# Power-SMPS.net
KiCad netlist of a schematic drawn in Altium Designer
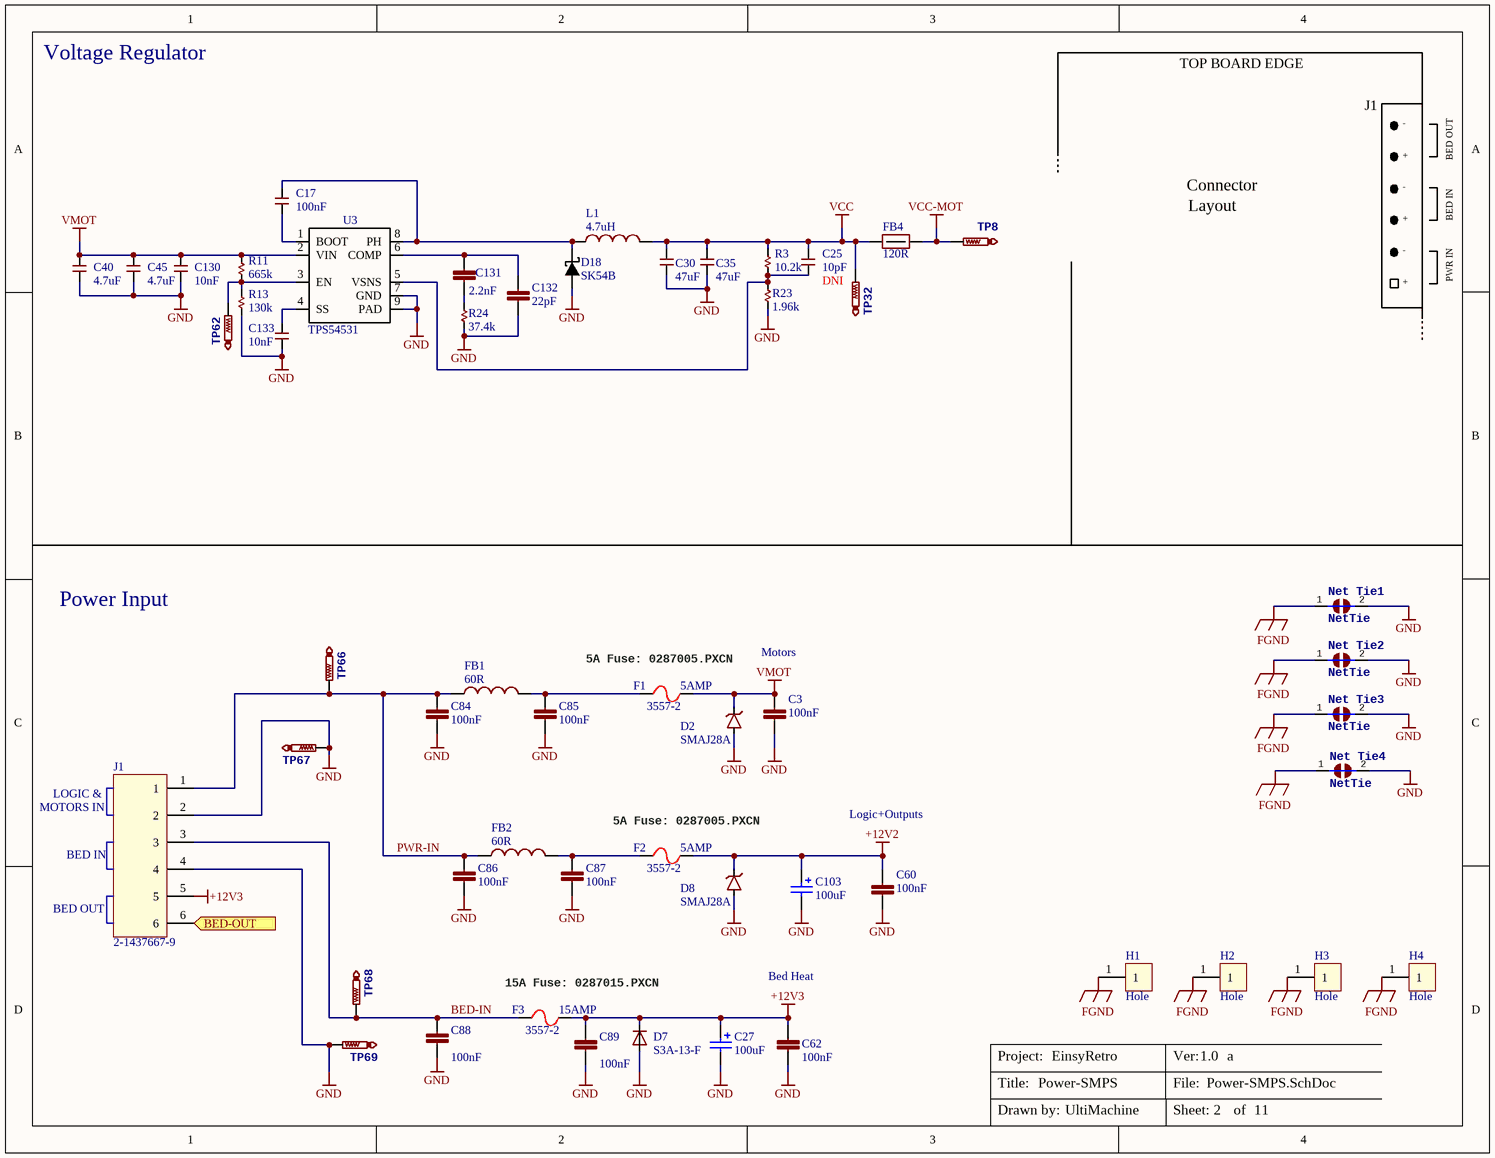
[diagram p0: Power-SMPS.SchDoc]

(export (version "E")
  (design (tool "Eeschema 10.0.6"))
  (components
    (comp (ref "C3")
      (value "100nF")
      (footprint "C0603")
      (description "CAP CER 0603 100nF 50V 10% X7R")
      (fields (field (name "MANUFACTURER") "Kemet") (field (name "TOLERANCE") "+/- 10%"))
      (libsource (lib "3Delight") (part "C0603C104K5RACTU"))
    )
    (comp (ref "C17")
      (value "100nF")
      (footprint "C0603")
      (description "CAP CER 0603 100nF 50V 10% X7R")
      (fields (field (name "MANUFACTURER") "Kemet") (field (name "TOLERANCE") "+/- 10%"))
      (libsource (lib "Capacitors") (part "100nF 0603 50V X7R"))
    )
    (comp (ref "C25")
      (value "10pF")
      (footprint "C0402")
      (description "CAP CER 10PF 50V 5% NP0 0402")
      (fields
        (field (name "TOLERANCE") "5%")
        (field (name "MANUFACTURER") "Samsung")
        (field (name "DNI") "DNI")
      )
      (libsource (lib "Capacitors") (part "10pF 0402 50V NP0"))
    )
    (comp (ref "C27")
      (value "100uF")
      (footprint "CAP-ELEC-063063077")
      (description "CAP ALUM 100UF 35V 20% SMD")
      (fields (field (name "MANUFACTURER") "Nichicon") (field (name "TOLERANCE") "+/- 20%"))
      (libsource (lib "3Delight") (part "UWT1V101MCL1GS"))
    )
    (comp (ref "C30")
      (value "47uF")
      (footprint "C1210")
      (description "CAP CER 47UF 10V X5R 1210")
      (fields (field (name "MANUFACTURER") "Murata") (field (name "TOLERANCE") "10%"))
      (libsource (lib "Capacitors") (part "47uF 1210 10V X5R"))
    )
    (comp (ref "C35")
      (value "47uF")
      (footprint "C1210")
      (description "CAP CER 47UF 10V X5R 1210")
      (fields (field (name "MANUFACTURER") "Murata") (field (name "TOLERANCE") "10%"))
      (libsource (lib "Capacitors") (part "47uF 1210 10V X5R"))
    )
    (comp (ref "C40")
      (value "4.7uF")
      (footprint "C1210")
      (description "CAP CER 4.7UF 50V X7R 1210")
      (fields (field (name "MANUFACTURER") "Murata") (field (name "PART") "4.7uF 1210 50V X7R"))
      (libsource (lib "Capacitors") (part "4.7uF 1210 50V X7R"))
    )
    (comp (ref "C45")
      (value "4.7uF")
      (footprint "C1210")
      (description "CAP CER 4.7UF 50V X7R 1210")
      (fields (field (name "MANUFACTURER") "Murata") (field (name "PART") "4.7uF 1210 50V X7R"))
      (libsource (lib "Capacitors") (part "4.7uF 1210 50V X7R"))
    )
    (comp (ref "C60")
      (value "100nF")
      (footprint "C0603")
      (description "CAP CER 0603 100nF 50V 10% X7R")
      (fields (field (name "MANUFACTURER") "Kemet") (field (name "TOLERANCE") "+/- 10%"))
      (libsource (lib "3Delight") (part "C0603C104K5RACTU"))
    )
    (comp (ref "C62")
      (value "100nF")
      (footprint "C0603")
      (description "CAP CER 0603 100nF 50V 10% X7R")
      (fields (field (name "MANUFACTURER") "Kemet") (field (name "TOLERANCE") "+/- 10%"))
      (libsource (lib "3Delight") (part "C0603C104K5RACTU"))
    )
    (comp (ref "C84")
      (value "100nF")
      (footprint "C0603")
      (description "CAP CER 0603 100nF 50V 10% X7R")
      (fields (field (name "MANUFACTURER") "Kemet") (field (name "TOLERANCE") "+/- 10%"))
      (libsource (lib "3Delight") (part "C0603C104K5RACTU"))
    )
    (comp (ref "C85")
      (value "100nF")
      (footprint "C0603")
      (description "CAP CER 0603 100nF 50V 10% X7R")
      (fields (field (name "MANUFACTURER") "Kemet") (field (name "TOLERANCE") "+/- 10%"))
      (libsource (lib "3Delight") (part "C0603C104K5RACTU"))
    )
    (comp (ref "C86")
      (value "100nF")
      (footprint "C0603")
      (description "CAP CER 0603 100nF 50V 10% X7R")
      (fields (field (name "MANUFACTURER") "Kemet") (field (name "TOLERANCE") "+/- 10%"))
      (libsource (lib "3Delight") (part "C0603C104K5RACTU"))
    )
    (comp (ref "C87")
      (value "100nF")
      (footprint "C0603")
      (description "CAP CER 0603 100nF 50V 10% X7R")
      (fields (field (name "MANUFACTURER") "Kemet") (field (name "TOLERANCE") "+/- 10%"))
      (libsource (lib "3Delight") (part "C0603C104K5RACTU"))
    )
    (comp (ref "C88")
      (value "100nF")
      (footprint "C0603")
      (description "CAP CER 0603 100nF 50V 10% X7R")
      (fields (field (name "MANUFACTURER") "Kemet") (field (name "TOLERANCE") "+/- 10%"))
      (libsource (lib "3Delight") (part "C0603C104K5RACTU"))
    )
    (comp (ref "C89")
      (value "100nF")
      (footprint "C0603")
      (description "CAP CER 0603 100nF 50V 10% X7R")
      (fields (field (name "MANUFACTURER") "Kemet") (field (name "TOLERANCE") "+/- 10%"))
      (libsource (lib "3Delight") (part "C0603C104K5RACTU"))
    )
    (comp (ref "C103")
      (value "100uF")
      (footprint "CAP-ELEC-063063077")
      (description "CAP ALUM 100UF 35V 20% SMD")
      (fields (field (name "MANUFACTURER") "Nichicon") (field (name "TOLERANCE") "+/- 20%"))
      (libsource (lib "3Delight") (part "UWT1V101MCL1GS"))
    )
    (comp (ref "C130")
      (value "10nF")
      (footprint "C0402")
      (description "CAP CER 10nF 50V X7R 0402")
      (fields (field (name "TOLERANCE") "5%") (field (name "MANUFACTURER") "Murata"))
      (libsource (lib "Capacitors") (part "10nF 0402 50V X7R"))
    )
    (comp (ref "C131")
      (value "2.2nF")
      (footprint "C0402")
      (description "CAP CER 0402 2.2nF 25V C0G")
      (fields (field (name "MANUFACTURER") "Kemet") (field (name "PART") "2.2nF 25V C0G 0402"))
      (libsource (lib "Capacitors") (part "2.2nF 25V C0G 0402"))
    )
    (comp (ref "C132")
      (value "22pF")
      (footprint "C0402")
      (description "CAP CER 0402 22pF 50V 5% C0G")
      (fields (field (name "MANUFACTURER") "AVX") (field (name "PART") "22pF 50V"))
      (libsource (lib "Capacitors") (part "22pF 0402 50V C0G"))
    )
    (comp (ref "C133")
      (value "10nF")
      (footprint "C0402")
      (description "CAP CER 10nF 50V X7R 0402")
      (fields (field (name "TOLERANCE") "5%") (field (name "MANUFACTURER") "Murata"))
      (libsource (lib "Capacitors") (part "10nF 0402 50V X7R"))
    )
    (comp (ref "D2")
      (value "SMAJ28A")
      (footprint "SMA-SM")
      (description "TVS DIODE 28VWM 45.4VC SMA")
      (fields (field (name "MANUFACTURER") "Diodes Inc") (field (name "TOLERANCE") "NA"))
      (libsource (lib "Diodes") (part "SMAJ28A"))
    )
    (comp (ref "D7")
      (value "S3A-13-F")
      (footprint "DO-214AB")
      (description "DIODE DO-214AB")
      (fields (field (name "MANUFACTURER") "Diodes Incorporated") (field (name "TOLERANCE") "NA"))
      (libsource (lib "3Delight") (part "S3A-13-F"))
    )
    (comp (ref "D8")
      (value "SMAJ28A")
      (footprint "SMA-SM")
      (description "TVS DIODE 28VWM 45.4VC SMA")
      (fields (field (name "MANUFACTURER") "Diodes Inc") (field (name "TOLERANCE") "NA"))
      (libsource (lib "Diodes") (part "SMAJ28A"))
    )
    (comp (ref "D18")
      (value "SK54B")
      (footprint "SMB_DO-214AA_LRG")
      (description "DIODE SCHOTTKY 40V 5A SMB_DO214AA")
      (fields (field (name "MANUFACTURER") "MCC") (field (name "VOLTAGE") "40Vrb"))
      (libsource (lib "Diodes") (part "SK54B"))
    )
    (comp (ref "F1")
      (value "3557-2")
      (footprint "3557")
      (description "FUSE PTH ATO")
      (fields (field (name "MANUFACTURER") "Keystone") (field (name "PART") "Fuse"))
      (libsource (lib "3Delight") (part "3557-2"))
    )
    (comp (ref "F2")
      (value "3557-2")
      (footprint "3557")
      (description "FUSE PTH ATO")
      (fields (field (name "MANUFACTURER") "Keystone") (field (name "PART") "Fuse"))
      (libsource (lib "3Delight") (part "3557-2"))
    )
    (comp (ref "F3")
      (value "3557-2")
      (footprint "3557")
      (description "FUSE PTH ATO")
      (fields (field (name "MANUFACTURER") "Keystone") (field (name "PART") "Fuse"))
      (libsource (lib "3Delight") (part "3557-2"))
    )
    (comp (ref "FB1")
      (value "60R")
      (footprint "3Delight:L1806")
      (description "FERRITE BEAD 1806 60ohm")
      (fields (field (name "MANUFACTURER") "Murata") (field (name "PART") "60Rf"))
      (libsource (lib "3Delight") (part "BLM41PG600SN1L"))
    )
    (comp (ref "FB2")
      (value "60R")
      (footprint "3Delight:L1806")
      (description "FERRITE BEAD 1806 60ohm")
      (fields (field (name "MANUFACTURER") "Murata") (field (name "PART") "60Rf"))
      (libsource (lib "3Delight") (part "BLM41PG600SN1L"))
    )
    (comp (ref "FB4")
      (value "120R")
      (footprint "FB0603")
      (description "FERRITE BEAD 120 OHM 0603 1LN")
      (fields (field (name "MANUFACTURER") "Samsung") (field (name "PART") "FERRITE 120R 3A 0603"))
      (libsource (lib "3Delight") (part "FERRITE 220R 2.5A 0603"))
    )
    (comp (ref "H1")
      (value "Hole")
      (footprint "Wave_hole_3x7-singleSided")
      (libsource (lib "3Delight") (part "Hole"))
    )
    (comp (ref "H2")
      (value "Hole")
      (footprint "Wave_hole_3x7-singleSided")
      (libsource (lib "3Delight") (part "Hole"))
    )
    (comp (ref "H3")
      (value "Hole")
      (footprint "Wave_hole_3x7-singleSided")
      (libsource (lib "3Delight") (part "Hole"))
    )
    (comp (ref "H4")
      (value "Hole")
      (footprint "Wave_hole_3x7-singleSided")
      (libsource (lib "3Delight") (part "Hole"))
    )
    (comp (ref "J1")
      (value "2-1437667-9")
      (footprint "CON-Barrier-6-8.26mm")
      (description "CONN BARRIER STRIP 6CIRC 0.325\"")
      (fields (field (name "MANUFACTURER") "TE") (field (name "PART") "6POS"))
      (libsource (lib "3Delight") (part "2-1437667-9"))
    )
    (comp (ref "L1")
      (value "4.7uH")
      (footprint "IND_10X10")
      (description "FIXED IND 4.7UH 10A 15.5 MOHM")
      (fields (field (name "MANUFACTURER") "Bourns") (field (name "PART") "4.7uH 10A"))
      (libsource (lib "Inductors") (part "4.7uH 10A"))
    )
    (comp (ref "Net Tie1")
      (value "NetTie")
      (footprint "Net Tie")
      (description "Net Tie")
      (fields (field (name "PUBLISHER") "UltiMachine"))
      (libsource (lib "3Delight") (part "NetTie"))
    )
    (comp (ref "Net Tie2")
      (value "NetTie")
      (footprint "Net Tie")
      (description "Net Tie")
      (fields (field (name "PUBLISHER") "UltiMachine"))
      (libsource (lib "3Delight") (part "NetTie"))
    )
    (comp (ref "Net Tie3")
      (value "NetTie")
      (footprint "Net Tie")
      (description "Net Tie")
      (fields (field (name "PUBLISHER") "UltiMachine"))
      (libsource (lib "3Delight") (part "NetTie"))
    )
    (comp (ref "Net Tie4")
      (value "NetTie")
      (footprint "Net Tie")
      (description "Net Tie")
      (fields (field (name "PUBLISHER") "UltiMachine"))
      (libsource (lib "3Delight") (part "NetTie"))
    )
    (comp (ref "R3")
      (value "10.2k")
      (footprint "R0402")
      (description "RES SMD 10.2K OHM 1% 1/16W 0402")
      (fields (field (name "MANUFACTURER") "Yageo") (field (name "PART") "10.2k 1% 0402"))
      (libsource (lib "Resistors") (part "10.2k 1% 0402"))
    )
    (comp (ref "R11")
      (value "665k")
      (footprint "R0402")
      (description "RES SMD 665K OHM 1% 1/16W 0402")
      (fields (field (name "MANUFACTURER") "Yageo") (field (name "PART") "665k 1% 0402"))
      (libsource (lib "Resistors") (part "665k 1% 0402"))
    )
    (comp (ref "R13")
      (value "130k")
      (footprint "Passives:R0402")
      (description "RES SMD 130K OHM 5% 1/16W 0402")
      (fields (field (name "MANUFACTURER") "Yageo") (field (name "PART") "130k 1% 0402"))
      (libsource (lib "Resistors") (part "130k 1% 0402"))
    )
    (comp (ref "R23")
      (value "1.96k")
      (footprint "R0402")
      (description "RES SMD 1.96K OHM 1% 1/16W 0402")
      (fields (field (name "MANUFACTURER") "Yageo") (field (name "PART") "1.96k 1% 0402"))
      (libsource (lib "Resistors") (part "1.96k 1% 0402"))
    )
    (comp (ref "R24")
      (value "37.4k")
      (footprint "R0402")
      (description "RES SMD 37.4K OHM 1% 1/16W 0402")
      (fields (field (name "MANUFACTURER") "Yageo") (field (name "TOLERANCE") "1%"))
      (libsource (lib "Resistors") (part "37.4K 1% 0402"))
    )
    (comp (ref "TP8")
      (value "TestPoint")
      (footprint "TP1-27")
      (description "Test Point")
      (libsource (lib "3Delight") (part "TestPoint"))
    )
    (comp (ref "TP32")
      (value "TestPoint")
      (footprint "TP1-27")
      (description "Test Point")
      (libsource (lib "") (part "TestPoint_2"))
    )
    (comp (ref "TP62")
      (value "TestPoint")
      (footprint "TP1-27")
      (description "Test Point")
      (libsource (lib "") (part "TestPoint_2"))
    )
    (comp (ref "TP66")
      (value "TestPoint")
      (footprint "TP1-27")
      (description "Test Point")
      (libsource (lib "") (part "TestPoint_1"))
    )
    (comp (ref "TP67")
      (value "TestPoint")
      (footprint "TP1-27")
      (description "Test Point")
      (libsource (lib "") (part "TestPoint_3"))
    )
    (comp (ref "TP68")
      (value "TestPoint")
      (footprint "TP1-27")
      (description "Test Point")
      (libsource (lib "") (part "TestPoint_1"))
    )
    (comp (ref "TP69")
      (value "TestPoint")
      (footprint "TP1-27")
      (description "Test Point")
      (libsource (lib "3Delight") (part "TestPoint"))
    )
    (comp (ref "U3")
      (value "TPS54531")
      (footprint "SOIC127P600X170_HS-9L")
      (description "IC REG BUCK ADJ 5A 8SOPWRPAD")
      (fields (field (name "MANUFACTURER") "TI"))
      (libsource (lib "ICs-Power") (part "TPS54531"))
    )
  )
  (nets
    (net (code "1") (name "+12V2") (class "Default")
      (node (ref "C103") (pin "1") (pinfunction "1_1") (pintype "passive"))
      (node (ref "C60") (pin "1") (pinfunction "1_1") (pintype "passive"))
      (node (ref "D8") (pin "K") (pinfunction "K_K") (pintype "passive"))
      (node (ref "F2") (pin "2") (pinfunction "2_2") (pintype "passive"))
    )
    (net (code "2") (name "+12V3") (class "Default")
      (node (ref "C27") (pin "1") (pinfunction "1_1") (pintype "passive"))
      (node (ref "C62") (pin "1") (pinfunction "1_1") (pintype "passive"))
      (node (ref "C89") (pin "1") (pinfunction "1_1") (pintype "passive"))
      (node (ref "D7") (pin "C") (pinfunction "C_C") (pintype "passive"))
      (node (ref "F3") (pin "2") (pinfunction "2_2") (pintype "passive"))
      (node (ref "J1") (pin "5") (pinfunction "5_5") (pintype "passive"))
    )
    (net (code "3") (name "/BED-IN") (class "Default")
      (node (ref "C88") (pin "1") (pinfunction "1_1") (pintype "passive"))
      (node (ref "F3") (pin "1") (pinfunction "1_1") (pintype "passive"))
      (node (ref "J1") (pin "3") (pinfunction "3_3") (pintype "passive"))
      (node (ref "TP68") (pin "TP") (pinfunction "TP_TP") (pintype "passive"))
    )
    (net (code "4") (name "/BED-OUT") (class "Default")
      (node (ref "J1") (pin "6") (pinfunction "6_6") (pintype "passive"))
    )
    (net (code "5") (name "/PWR-IN") (class "Default")
      (node (ref "C84") (pin "1") (pinfunction "1_1") (pintype "passive"))
      (node (ref "C86") (pin "1") (pinfunction "1_1") (pintype "passive"))
      (node (ref "FB1") (pin "1") (pinfunction "1_1") (pintype "passive"))
      (node (ref "FB2") (pin "1") (pinfunction "1_1") (pintype "passive"))
      (node (ref "J1") (pin "1") (pinfunction "1_1") (pintype "passive"))
      (node (ref "TP66") (pin "TP") (pinfunction "TP_TP") (pintype "passive"))
    )
    (net (code "6") (name "FGND") (class "Default")
      (node (ref "H1") (pin "1") (pinfunction "1_1") (pintype "power_in"))
      (node (ref "H2") (pin "1") (pinfunction "1_1") (pintype "power_in"))
      (node (ref "H3") (pin "1") (pinfunction "1_1") (pintype "power_in"))
      (node (ref "H4") (pin "1") (pinfunction "1_1") (pintype "power_in"))
      (node (ref "Net Tie1") (pin "1") (pinfunction "1_1") (pintype "passive"))
      (node (ref "Net Tie2") (pin "1") (pinfunction "1_1") (pintype "passive"))
      (node (ref "Net Tie3") (pin "1") (pinfunction "1_1") (pintype "passive"))
      (node (ref "Net Tie4") (pin "1") (pinfunction "1_1") (pintype "passive"))
    )
    (net (code "7") (name "GND") (class "Default")
      (node (ref "C103") (pin "2") (pinfunction "2_2") (pintype "passive"))
      (node (ref "C130") (pin "1") (pinfunction "1_1") (pintype "passive"))
      (node (ref "C132") (pin "1") (pinfunction "1_1") (pintype "passive"))
      (node (ref "C133") (pin "1") (pinfunction "1_1") (pintype "passive"))
      (node (ref "C27") (pin "2") (pinfunction "2_2") (pintype "passive"))
      (node (ref "C3") (pin "2") (pinfunction "2_2") (pintype "passive"))
      (node (ref "C30") (pin "1") (pinfunction "1_1") (pintype "passive"))
      (node (ref "C35") (pin "1") (pinfunction "1_1") (pintype "passive"))
      (node (ref "C40") (pin "1") (pinfunction "1_1") (pintype "passive"))
      (node (ref "C45") (pin "1") (pinfunction "1_1") (pintype "passive"))
      (node (ref "C60") (pin "2") (pinfunction "2_2") (pintype "passive"))
      (node (ref "C62") (pin "2") (pinfunction "2_2") (pintype "passive"))
      (node (ref "C84") (pin "2") (pinfunction "2_2") (pintype "passive"))
      (node (ref "C85") (pin "2") (pinfunction "2_2") (pintype "passive"))
      (node (ref "C86") (pin "2") (pinfunction "2_2") (pintype "passive"))
      (node (ref "C87") (pin "2") (pinfunction "2_2") (pintype "passive"))
      (node (ref "C88") (pin "2") (pinfunction "2_2") (pintype "passive"))
      (node (ref "C89") (pin "2") (pinfunction "2_2") (pintype "passive"))
      (node (ref "D18") (pin "A") (pinfunction "ANODE_A") (pintype "passive"))
      (node (ref "D2") (pin "A") (pinfunction "A_A") (pintype "passive"))
      (node (ref "D7") (pin "A") (pinfunction "A_A") (pintype "passive"))
      (node (ref "D8") (pin "A") (pinfunction "A_A") (pintype "passive"))
      (node (ref "J1") (pin "2") (pinfunction "2_2") (pintype "passive"))
      (node (ref "J1") (pin "4") (pinfunction "4_4") (pintype "passive"))
      (node (ref "Net Tie1") (pin "2") (pinfunction "2_2") (pintype "passive"))
      (node (ref "Net Tie2") (pin "2") (pinfunction "2_2") (pintype "passive"))
      (node (ref "Net Tie3") (pin "2") (pinfunction "2_2") (pintype "passive"))
      (node (ref "Net Tie4") (pin "2") (pinfunction "2_2") (pintype "passive"))
      (node (ref "R13") (pin "1") (pinfunction "1_1") (pintype "passive"))
      (node (ref "R23") (pin "1") (pinfunction "1_1") (pintype "passive"))
      (node (ref "R24") (pin "1") (pinfunction "1_1") (pintype "passive"))
      (node (ref "TP67") (pin "TP") (pinfunction "TP_TP") (pintype "passive"))
      (node (ref "TP69") (pin "TP") (pinfunction "TP_TP") (pintype "passive"))
      (node (ref "U3") (pin "7") (pinfunction "GND_7") (pintype "passive"))
      (node (ref "U3") (pin "9") (pinfunction "PAD_9") (pintype "passive"))
    )
    (net (code "8") (name "Net-(C85-Pad1)") (class "Default")
      (node (ref "C85") (pin "1") (pinfunction "1_1") (pintype "passive"))
      (node (ref "F1") (pin "1") (pinfunction "1_1") (pintype "passive"))
      (node (ref "FB1") (pin "2") (pinfunction "2_2") (pintype "passive"))
    )
    (net (code "9") (name "Net-(C87-Pad1)") (class "Default")
      (node (ref "C87") (pin "1") (pinfunction "1_1") (pintype "passive"))
      (node (ref "F2") (pin "1") (pinfunction "1_1") (pintype "passive"))
      (node (ref "FB2") (pin "2") (pinfunction "2_2") (pintype "passive"))
    )
    (net (code "10") (name "Net-(C131-Pad1)") (class "Default")
      (node (ref "C131") (pin "1") (pinfunction "1_1") (pintype "passive"))
      (node (ref "R24") (pin "2") (pinfunction "2_2") (pintype "passive"))
    )
    (net (code "11") (name "Net-(D18-CATHODE)") (class "Default")
      (node (ref "C17") (pin "2") (pinfunction "2_2") (pintype "passive"))
      (node (ref "D18") (pin "K") (pinfunction "CATHODE_K") (pintype "passive"))
      (node (ref "L1") (pin "1") (pinfunction "1_1") (pintype "passive"))
      (node (ref "U3") (pin "8") (pinfunction "PH_8") (pintype "passive"))
    )
    (net (code "12") (name "Net-(U3-BOOT)") (class "Default")
      (node (ref "C17") (pin "1") (pinfunction "1_1") (pintype "passive"))
      (node (ref "U3") (pin "1") (pinfunction "BOOT_1") (pintype "passive"))
    )
    (net (code "13") (name "Net-(U3-COMP)") (class "Default")
      (node (ref "C131") (pin "2") (pinfunction "2_2") (pintype "passive"))
      (node (ref "C132") (pin "2") (pinfunction "2_2") (pintype "passive"))
      (node (ref "U3") (pin "6") (pinfunction "COMP_6") (pintype "passive"))
    )
    (net (code "14") (name "Net-(U3-EN)") (class "Default")
      (node (ref "R11") (pin "1") (pinfunction "1_1") (pintype "passive"))
      (node (ref "R13") (pin "2") (pinfunction "2_2") (pintype "passive"))
      (node (ref "TP62") (pin "TP") (pinfunction "TP_TP") (pintype "passive"))
      (node (ref "U3") (pin "3") (pinfunction "EN_3") (pintype "passive"))
    )
    (net (code "15") (name "Net-(U3-SS)") (class "Default")
      (node (ref "C133") (pin "2") (pinfunction "2_2") (pintype "passive"))
      (node (ref "U3") (pin "4") (pinfunction "SS_4") (pintype "passive"))
    )
    (net (code "16") (name "Net-(U3-VSNS)") (class "Default")
      (node (ref "C25") (pin "1") (pinfunction "1_1") (pintype "passive"))
      (node (ref "R23") (pin "2") (pinfunction "2_2") (pintype "passive"))
      (node (ref "R3") (pin "2") (pinfunction "2_2") (pintype "passive"))
      (node (ref "U3") (pin "5") (pinfunction "VSNS_5") (pintype "passive"))
    )
    (net (code "17") (name "VCC") (class "Default")
      (node (ref "C25") (pin "2") (pinfunction "2_2") (pintype "passive"))
      (node (ref "C30") (pin "2") (pinfunction "2_2") (pintype "passive"))
      (node (ref "C35") (pin "2") (pinfunction "2_2") (pintype "passive"))
      (node (ref "FB4") (pin "1") (pinfunction "1_1") (pintype "passive"))
      (node (ref "L1") (pin "2") (pinfunction "2_2") (pintype "passive"))
      (node (ref "R3") (pin "1") (pinfunction "1_1") (pintype "passive"))
      (node (ref "TP32") (pin "TP") (pinfunction "TP_TP") (pintype "passive"))
    )
    (net (code "18") (name "VCC-MOT") (class "Default")
      (node (ref "FB4") (pin "2") (pinfunction "2_2") (pintype "passive"))
      (node (ref "TP8") (pin "TP") (pinfunction "TP_TP") (pintype "passive"))
    )
    (net (code "19") (name "VMOT") (class "Default")
      (node (ref "C130") (pin "2") (pinfunction "2_2") (pintype "passive"))
      (node (ref "C3") (pin "1") (pinfunction "1_1") (pintype "passive"))
      (node (ref "C40") (pin "2") (pinfunction "2_2") (pintype "passive"))
      (node (ref "C45") (pin "2") (pinfunction "2_2") (pintype "passive"))
      (node (ref "D2") (pin "K") (pinfunction "K_K") (pintype "passive"))
      (node (ref "F1") (pin "2") (pinfunction "2_2") (pintype "passive"))
      (node (ref "R11") (pin "2") (pinfunction "2_2") (pintype "passive"))
      (node (ref "U3") (pin "2") (pinfunction "VIN_2") (pintype "passive"))
    )
  )
)
